# W104C.net
KiCad netlist of a schematic drawn in EAGLE
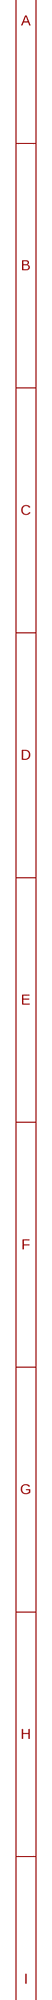
[diagram p0: schematic, sheet 1, part 1 of 2]
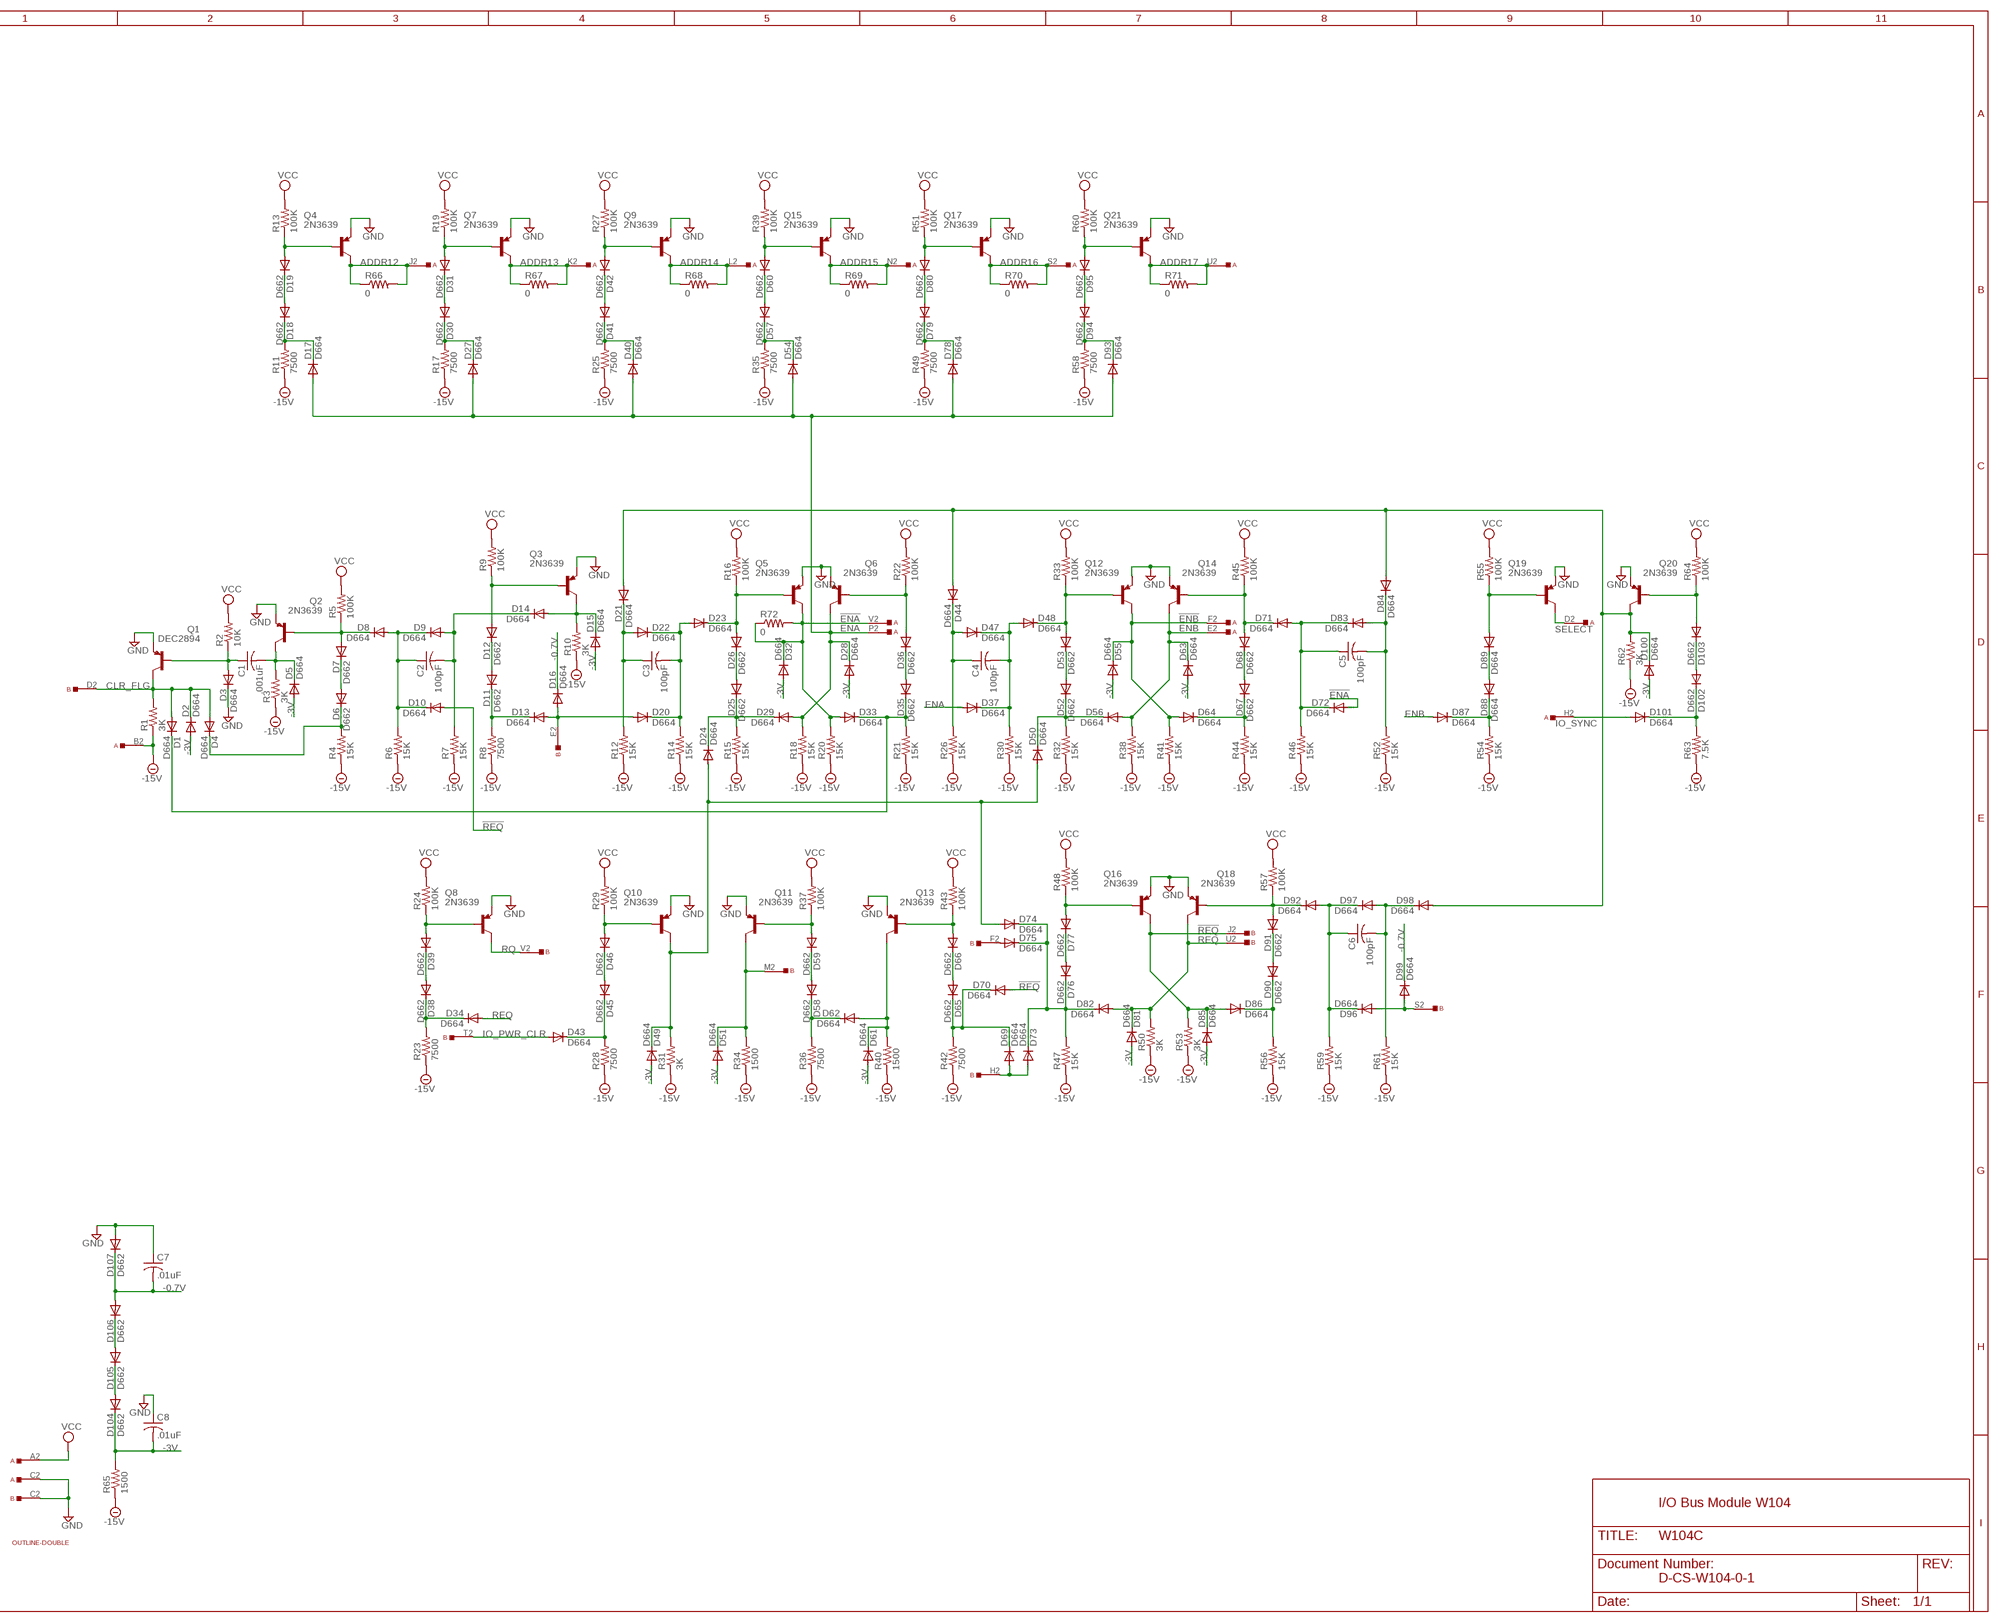
[diagram p1: schematic, sheet 1, part 2 of 2]

(export (version "E")
  (design (tool "Eeschema 10.0.6"))
  (components
    (comp (ref "A")
      (value "SS-TOP")
      (footprint "eagle-import:EDGE-CON1")
      (libsource (lib "eagle-import") (part "SS-TOP"))
    )
    (comp (ref "B")
      (value "SS-TOP")
      (footprint "eagle-import:EDGE-CON1")
      (libsource (lib "eagle-import") (part "SS-TOP"))
    )
    (comp (ref "C1")
      (value ".001uF")
      (footprint "eagle-import:C063-025X075")
      (libsource (lib "eagle-import") (part "C-US"))
    )
    (comp (ref "C2")
      (value "100pF")
      (footprint "eagle-import:C150-054X183")
      (libsource (lib "eagle-import") (part "C-US150-054X183"))
    )
    (comp (ref "C3")
      (value "100pF")
      (footprint "eagle-import:C150-054X183")
      (libsource (lib "eagle-import") (part "C-US150-054X183"))
    )
    (comp (ref "C4")
      (value "100pF")
      (footprint "eagle-import:C150-054X183")
      (libsource (lib "eagle-import") (part "C-US150-054X183"))
    )
    (comp (ref "C5")
      (value "100pF")
      (footprint "eagle-import:C150-054X183")
      (libsource (lib "eagle-import") (part "C-US150-054X183"))
    )
    (comp (ref "C6")
      (value "100pF")
      (footprint "eagle-import:C150-054X183")
      (libsource (lib "eagle-import") (part "C-US150-054X183"))
    )
    (comp (ref "C7")
      (value ".01uF")
      (footprint "eagle-import:C063-025X075")
      (libsource (lib "eagle-import") (part "C-US"))
    )
    (comp (ref "C8")
      (value ".01uF")
      (footprint "eagle-import:C063-025X075")
      (libsource (lib "eagle-import") (part "C-US"))
    )
    (comp (ref "D1")
      (value "D664")
      (footprint "eagle-import:DO35-10")
      (libsource (lib "eagle-import") (part "DIODE-DO35-10"))
    )
    (comp (ref "D2")
      (value "D664")
      (footprint "eagle-import:DO35-10")
      (libsource (lib "eagle-import") (part "DIODE-DO35-10"))
    )
    (comp (ref "D3")
      (value "D664")
      (footprint "eagle-import:DO35-10")
      (libsource (lib "eagle-import") (part "DIODE-DO35-10"))
    )
    (comp (ref "D4")
      (value "D664")
      (footprint "eagle-import:DO35-10")
      (libsource (lib "eagle-import") (part "DIODE-DO35-10"))
    )
    (comp (ref "D5")
      (value "D664")
      (footprint "eagle-import:DO35-10")
      (libsource (lib "eagle-import") (part "DIODE-DO35-10"))
    )
    (comp (ref "D6")
      (value "D662")
      (footprint "eagle-import:DO35-10")
      (libsource (lib "eagle-import") (part "DIODE-DO35-10"))
    )
    (comp (ref "D7")
      (value "D662")
      (footprint "eagle-import:DO35-10")
      (libsource (lib "eagle-import") (part "DIODE-DO35-10"))
    )
    (comp (ref "D8")
      (value "D664")
      (footprint "eagle-import:DO35-10")
      (libsource (lib "eagle-import") (part "DIODE-DO35-10"))
    )
    (comp (ref "D9")
      (value "D664")
      (footprint "eagle-import:DO35-10")
      (libsource (lib "eagle-import") (part "DIODE-DO35-10"))
    )
    (comp (ref "D10")
      (value "D664")
      (footprint "eagle-import:DO35-10")
      (libsource (lib "eagle-import") (part "DIODE-DO35-10"))
    )
    (comp (ref "D11")
      (value "D662")
      (footprint "eagle-import:DO35-10")
      (libsource (lib "eagle-import") (part "DIODE-DO35-10"))
    )
    (comp (ref "D12")
      (value "D662")
      (footprint "eagle-import:DO35-10")
      (libsource (lib "eagle-import") (part "DIODE-DO35-10"))
    )
    (comp (ref "D13")
      (value "D664")
      (footprint "eagle-import:DO35-10")
      (libsource (lib "eagle-import") (part "DIODE-DO35-10"))
    )
    (comp (ref "D14")
      (value "D664")
      (footprint "eagle-import:DO35-10")
      (libsource (lib "eagle-import") (part "DIODE-DO35-10"))
    )
    (comp (ref "D15")
      (value "D664")
      (footprint "eagle-import:DO35-10")
      (libsource (lib "eagle-import") (part "DIODE-DO35-10"))
    )
    (comp (ref "D16")
      (value "D664")
      (footprint "eagle-import:DO35-10")
      (libsource (lib "eagle-import") (part "DIODE-DO35-10"))
    )
    (comp (ref "D17")
      (value "D664")
      (footprint "eagle-import:DO35-10")
      (libsource (lib "eagle-import") (part "DIODE-DO35-10"))
    )
    (comp (ref "D18")
      (value "D662")
      (footprint "eagle-import:DO35-10")
      (libsource (lib "eagle-import") (part "DIODE-DO35-10"))
    )
    (comp (ref "D19")
      (value "D662")
      (footprint "eagle-import:DO35-10")
      (libsource (lib "eagle-import") (part "DIODE-DO35-10"))
    )
    (comp (ref "D20")
      (value "D664")
      (footprint "eagle-import:DO35-10")
      (libsource (lib "eagle-import") (part "DIODE-DO35-10"))
    )
    (comp (ref "D21")
      (value "D664")
      (footprint "eagle-import:DO35-10")
      (libsource (lib "eagle-import") (part "DIODE-DO35-10"))
    )
    (comp (ref "D22")
      (value "D664")
      (footprint "eagle-import:DO35-10")
      (libsource (lib "eagle-import") (part "DIODE-DO35-10"))
    )
    (comp (ref "D23")
      (value "D664")
      (footprint "eagle-import:DO35-10")
      (libsource (lib "eagle-import") (part "DIODE-DO35-10"))
    )
    (comp (ref "D24")
      (value "D664")
      (footprint "eagle-import:DO35-10")
      (libsource (lib "eagle-import") (part "DIODE-DO35-10"))
    )
    (comp (ref "D25")
      (value "D662")
      (footprint "eagle-import:DO35-10")
      (libsource (lib "eagle-import") (part "DIODE-DO35-10"))
    )
    (comp (ref "D26")
      (value "D662")
      (footprint "eagle-import:DO35-10")
      (libsource (lib "eagle-import") (part "DIODE-DO35-10"))
    )
    (comp (ref "D27")
      (value "D664")
      (footprint "eagle-import:DO35-10")
      (libsource (lib "eagle-import") (part "DIODE-DO35-10"))
    )
    (comp (ref "D28")
      (value "D664")
      (footprint "eagle-import:DO35-10")
      (libsource (lib "eagle-import") (part "DIODE-DO35-10"))
    )
    (comp (ref "D29")
      (value "D664")
      (footprint "eagle-import:DO35-10")
      (libsource (lib "eagle-import") (part "DIODE-DO35-10"))
    )
    (comp (ref "D30")
      (value "D662")
      (footprint "eagle-import:DO35-10")
      (libsource (lib "eagle-import") (part "DIODE-DO35-10"))
    )
    (comp (ref "D31")
      (value "D662")
      (footprint "eagle-import:DO35-10")
      (libsource (lib "eagle-import") (part "DIODE-DO35-10"))
    )
    (comp (ref "D32")
      (value "D664")
      (footprint "eagle-import:DO35-10")
      (libsource (lib "eagle-import") (part "DIODE-DO35-10"))
    )
    (comp (ref "D33")
      (value "D664")
      (footprint "eagle-import:DO35-10")
      (libsource (lib "eagle-import") (part "DIODE-DO35-10"))
    )
    (comp (ref "D34")
      (value "D664")
      (footprint "eagle-import:DO35-10")
      (libsource (lib "eagle-import") (part "DIODE-DO35-10"))
    )
    (comp (ref "D35")
      (value "D662")
      (footprint "eagle-import:DO35-10")
      (libsource (lib "eagle-import") (part "DIODE-DO35-10"))
    )
    (comp (ref "D36")
      (value "D662")
      (footprint "eagle-import:DO35-10")
      (libsource (lib "eagle-import") (part "DIODE-DO35-10"))
    )
    (comp (ref "D37")
      (value "D664")
      (footprint "eagle-import:DO35-10")
      (libsource (lib "eagle-import") (part "DIODE-DO35-10"))
    )
    (comp (ref "D38")
      (value "D662")
      (footprint "eagle-import:DO35-10")
      (libsource (lib "eagle-import") (part "DIODE-DO35-10"))
    )
    (comp (ref "D39")
      (value "D662")
      (footprint "eagle-import:DO35-10")
      (libsource (lib "eagle-import") (part "DIODE-DO35-10"))
    )
    (comp (ref "D40")
      (value "D664")
      (footprint "eagle-import:DO35-10")
      (libsource (lib "eagle-import") (part "DIODE-DO35-10"))
    )
    (comp (ref "D41")
      (value "D662")
      (footprint "eagle-import:DO35-10")
      (libsource (lib "eagle-import") (part "DIODE-DO35-10"))
    )
    (comp (ref "D42")
      (value "D662")
      (footprint "eagle-import:DO35-10")
      (libsource (lib "eagle-import") (part "DIODE-DO35-10"))
    )
    (comp (ref "D43")
      (value "D664")
      (footprint "eagle-import:DO35-10")
      (libsource (lib "eagle-import") (part "DIODE-DO35-10"))
    )
    (comp (ref "D44")
      (value "D664")
      (footprint "eagle-import:DO35-10")
      (libsource (lib "eagle-import") (part "DIODE-DO35-10"))
    )
    (comp (ref "D45")
      (value "D662")
      (footprint "eagle-import:DO35-10")
      (libsource (lib "eagle-import") (part "DIODE-DO35-10"))
    )
    (comp (ref "D46")
      (value "D662")
      (footprint "eagle-import:DO35-10")
      (libsource (lib "eagle-import") (part "DIODE-DO35-10"))
    )
    (comp (ref "D47")
      (value "D664")
      (footprint "eagle-import:DO35-10")
      (libsource (lib "eagle-import") (part "DIODE-DO35-10"))
    )
    (comp (ref "D48")
      (value "D664")
      (footprint "eagle-import:DO35-10")
      (libsource (lib "eagle-import") (part "DIODE-DO35-10"))
    )
    (comp (ref "D49")
      (value "D664")
      (footprint "eagle-import:DO35-10")
      (libsource (lib "eagle-import") (part "DIODE-DO35-10"))
    )
    (comp (ref "D50")
      (value "D664")
      (footprint "eagle-import:DO35-10")
      (libsource (lib "eagle-import") (part "DIODE-DO35-10"))
    )
    (comp (ref "D51")
      (value "D664")
      (footprint "eagle-import:DO35-10")
      (libsource (lib "eagle-import") (part "DIODE-DO35-10"))
    )
    (comp (ref "D52")
      (value "D662")
      (footprint "eagle-import:DO35-10")
      (libsource (lib "eagle-import") (part "DIODE-DO35-10"))
    )
    (comp (ref "D53")
      (value "D662")
      (footprint "eagle-import:DO35-10")
      (libsource (lib "eagle-import") (part "DIODE-DO35-10"))
    )
    (comp (ref "D54")
      (value "D664")
      (footprint "eagle-import:DO35-10")
      (libsource (lib "eagle-import") (part "DIODE-DO35-10"))
    )
    (comp (ref "D55")
      (value "D664")
      (footprint "eagle-import:DO35-10")
      (libsource (lib "eagle-import") (part "DIODE-DO35-10"))
    )
    (comp (ref "D56")
      (value "D664")
      (footprint "eagle-import:DO35-10")
      (libsource (lib "eagle-import") (part "DIODE-DO35-10"))
    )
    (comp (ref "D57")
      (value "D662")
      (footprint "eagle-import:DO35-10")
      (libsource (lib "eagle-import") (part "DIODE-DO35-10"))
    )
    (comp (ref "D58")
      (value "D662")
      (footprint "eagle-import:DO35-10")
      (libsource (lib "eagle-import") (part "DIODE-DO35-10"))
    )
    (comp (ref "D59")
      (value "D662")
      (footprint "eagle-import:DO35-10")
      (libsource (lib "eagle-import") (part "DIODE-DO35-10"))
    )
    (comp (ref "D60")
      (value "D662")
      (footprint "eagle-import:DO35-10")
      (libsource (lib "eagle-import") (part "DIODE-DO35-10"))
    )
    (comp (ref "D61")
      (value "D664")
      (footprint "eagle-import:DO35-10")
      (libsource (lib "eagle-import") (part "DIODE-DO35-10"))
    )
    (comp (ref "D62")
      (value "D664")
      (footprint "eagle-import:DO35-10")
      (libsource (lib "eagle-import") (part "DIODE-DO35-10"))
    )
    (comp (ref "D63")
      (value "D664")
      (footprint "eagle-import:DO35-10")
      (libsource (lib "eagle-import") (part "DIODE-DO35-10"))
    )
    (comp (ref "D64")
      (value "D664")
      (footprint "eagle-import:DO35-10")
      (libsource (lib "eagle-import") (part "DIODE-DO35-10"))
    )
    (comp (ref "D65")
      (value "D662")
      (footprint "eagle-import:DO35-10")
      (libsource (lib "eagle-import") (part "DIODE-DO35-10"))
    )
    (comp (ref "D66")
      (value "D662")
      (footprint "eagle-import:DO35-10")
      (libsource (lib "eagle-import") (part "DIODE-DO35-10"))
    )
    (comp (ref "D67")
      (value "D662")
      (footprint "eagle-import:DO35-10")
      (libsource (lib "eagle-import") (part "DIODE-DO35-10"))
    )
    (comp (ref "D68")
      (value "D662")
      (footprint "eagle-import:DO35-10")
      (libsource (lib "eagle-import") (part "DIODE-DO35-10"))
    )
    (comp (ref "D69")
      (value "D664")
      (footprint "eagle-import:DO35-10")
      (libsource (lib "eagle-import") (part "DIODE-DO35-10"))
    )
    (comp (ref "D70")
      (value "D664")
      (footprint "eagle-import:DO35-10")
      (libsource (lib "eagle-import") (part "DIODE-DO35-10"))
    )
    (comp (ref "D71")
      (value "D664")
      (footprint "eagle-import:DO35-10")
      (libsource (lib "eagle-import") (part "DIODE-DO35-10"))
    )
    (comp (ref "D72")
      (value "D664")
      (footprint "eagle-import:DO35-10")
      (libsource (lib "eagle-import") (part "DIODE-DO35-10"))
    )
    (comp (ref "D73")
      (value "D664")
      (footprint "eagle-import:DO35-10")
      (libsource (lib "eagle-import") (part "DIODE-DO35-10"))
    )
    (comp (ref "D74")
      (value "D664")
      (footprint "eagle-import:DO35-10")
      (libsource (lib "eagle-import") (part "DIODE-DO35-10"))
    )
    (comp (ref "D75")
      (value "D664")
      (footprint "eagle-import:DO35-10")
      (libsource (lib "eagle-import") (part "DIODE-DO35-10"))
    )
    (comp (ref "D76")
      (value "D662")
      (footprint "eagle-import:DO35-10")
      (libsource (lib "eagle-import") (part "DIODE-DO35-10"))
    )
    (comp (ref "D77")
      (value "D662")
      (footprint "eagle-import:DO35-10")
      (libsource (lib "eagle-import") (part "DIODE-DO35-10"))
    )
    (comp (ref "D78")
      (value "D664")
      (footprint "eagle-import:DO35-10")
      (libsource (lib "eagle-import") (part "DIODE-DO35-10"))
    )
    (comp (ref "D79")
      (value "D662")
      (footprint "eagle-import:DO35-10")
      (libsource (lib "eagle-import") (part "DIODE-DO35-10"))
    )
    (comp (ref "D80")
      (value "D662")
      (footprint "eagle-import:DO35-10")
      (libsource (lib "eagle-import") (part "DIODE-DO35-10"))
    )
    (comp (ref "D81")
      (value "D664")
      (footprint "eagle-import:DO35-10")
      (libsource (lib "eagle-import") (part "DIODE-DO35-10"))
    )
    (comp (ref "D82")
      (value "D664")
      (footprint "eagle-import:DO35-10")
      (libsource (lib "eagle-import") (part "DIODE-DO35-10"))
    )
    (comp (ref "D83")
      (value "D664")
      (footprint "eagle-import:DO35-10")
      (libsource (lib "eagle-import") (part "DIODE-DO35-10"))
    )
    (comp (ref "D84")
      (value "D664")
      (footprint "eagle-import:DO35-10")
      (libsource (lib "eagle-import") (part "DIODE-DO35-10"))
    )
    (comp (ref "D85")
      (value "D664")
      (footprint "eagle-import:DO35-10")
      (libsource (lib "eagle-import") (part "DIODE-DO35-10"))
    )
    (comp (ref "D86")
      (value "D664")
      (footprint "eagle-import:DO35-10")
      (libsource (lib "eagle-import") (part "DIODE-DO35-10"))
    )
    (comp (ref "D87")
      (value "D664")
      (footprint "eagle-import:DO35-10")
      (libsource (lib "eagle-import") (part "DIODE-DO35-10"))
    )
    (comp (ref "D88")
      (value "D664")
      (footprint "eagle-import:DO35-10")
      (libsource (lib "eagle-import") (part "DIODE-DO35-10"))
    )
    (comp (ref "D89")
      (value "D664")
      (footprint "eagle-import:DO35-10")
      (libsource (lib "eagle-import") (part "DIODE-DO35-10"))
    )
    (comp (ref "D90")
      (value "D662")
      (footprint "eagle-import:DO35-10")
      (libsource (lib "eagle-import") (part "DIODE-DO35-10"))
    )
    (comp (ref "D91")
      (value "D662")
      (footprint "eagle-import:DO35-10")
      (libsource (lib "eagle-import") (part "DIODE-DO35-10"))
    )
    (comp (ref "D92")
      (value "D664")
      (footprint "eagle-import:DO35-10")
      (libsource (lib "eagle-import") (part "DIODE-DO35-10"))
    )
    (comp (ref "D93")
      (value "D664")
      (footprint "eagle-import:DO35-10")
      (libsource (lib "eagle-import") (part "DIODE-DO35-10"))
    )
    (comp (ref "D94")
      (value "D662")
      (footprint "eagle-import:DO35-10")
      (libsource (lib "eagle-import") (part "DIODE-DO35-10"))
    )
    (comp (ref "D95")
      (value "D662")
      (footprint "eagle-import:DO35-10")
      (libsource (lib "eagle-import") (part "DIODE-DO35-10"))
    )
    (comp (ref "D96")
      (value "D664")
      (footprint "eagle-import:DO35-10")
      (libsource (lib "eagle-import") (part "DIODE-DO35-10"))
    )
    (comp (ref "D97")
      (value "D664")
      (footprint "eagle-import:DO35-10")
      (libsource (lib "eagle-import") (part "DIODE-DO35-10"))
    )
    (comp (ref "D98")
      (value "D664")
      (footprint "eagle-import:DO35-10")
      (libsource (lib "eagle-import") (part "DIODE-DO35-10"))
    )
    (comp (ref "D99")
      (value "D664")
      (footprint "eagle-import:DO35-10")
      (libsource (lib "eagle-import") (part "DIODE-DO35-10"))
    )
    (comp (ref "D100")
      (value "D664")
      (footprint "eagle-import:DO35-10")
      (libsource (lib "eagle-import") (part "DIODE-DO35-10"))
    )
    (comp (ref "D101")
      (value "D664")
      (footprint "eagle-import:DO35-10")
      (libsource (lib "eagle-import") (part "DIODE-DO35-10"))
    )
    (comp (ref "D102")
      (value "D662")
      (footprint "eagle-import:DO35-10")
      (libsource (lib "eagle-import") (part "DIODE-DO35-10"))
    )
    (comp (ref "D103")
      (value "D662")
      (footprint "eagle-import:DO35-10")
      (libsource (lib "eagle-import") (part "DIODE-DO35-10"))
    )
    (comp (ref "D104")
      (value "D662")
      (footprint "eagle-import:DO35-10")
      (libsource (lib "eagle-import") (part "DIODE-DO35-10"))
    )
    (comp (ref "D105")
      (value "D662")
      (footprint "eagle-import:DO35-10")
      (libsource (lib "eagle-import") (part "DIODE-DO35-10"))
    )
    (comp (ref "D106")
      (value "D662")
      (footprint "eagle-import:DO35-10")
      (libsource (lib "eagle-import") (part "DIODE-DO35-10"))
    )
    (comp (ref "D107")
      (value "D662")
      (footprint "eagle-import:DO35-10")
      (libsource (lib "eagle-import") (part "DIODE-DO35-10"))
    )
    (comp (ref "Q1")
      (value "DEC2894")
      (footprint "eagle-import:TO5")
      (libsource (lib "eagle-import") (part "-PNP-TO5"))
    )
    (comp (ref "Q2")
      (value "2N3639")
      (footprint "eagle-import:TO5")
      (libsource (lib "eagle-import") (part "-PNP-TO5"))
    )
    (comp (ref "Q3")
      (value "2N3639")
      (footprint "eagle-import:TO5")
      (libsource (lib "eagle-import") (part "-PNP-TO5"))
    )
    (comp (ref "Q4")
      (value "2N3639")
      (footprint "eagle-import:TO5")
      (libsource (lib "eagle-import") (part "-PNP-TO5"))
    )
    (comp (ref "Q5")
      (value "2N3639")
      (footprint "eagle-import:TO5")
      (libsource (lib "eagle-import") (part "-PNP-TO5"))
    )
    (comp (ref "Q6")
      (value "2N3639")
      (footprint "eagle-import:TO5")
      (libsource (lib "eagle-import") (part "-PNP-TO5"))
    )
    (comp (ref "Q7")
      (value "2N3639")
      (footprint "eagle-import:TO5")
      (libsource (lib "eagle-import") (part "-PNP-TO5"))
    )
    (comp (ref "Q8")
      (value "2N3639")
      (footprint "eagle-import:TO5")
      (libsource (lib "eagle-import") (part "-PNP-TO5"))
    )
    (comp (ref "Q9")
      (value "2N3639")
      (footprint "eagle-import:TO5")
      (libsource (lib "eagle-import") (part "-PNP-TO5"))
    )
    (comp (ref "Q10")
      (value "2N3639")
      (footprint "eagle-import:TO5")
      (libsource (lib "eagle-import") (part "-PNP-TO5"))
    )
    (comp (ref "Q11")
      (value "2N3639")
      (footprint "eagle-import:TO5")
      (libsource (lib "eagle-import") (part "-PNP-TO5"))
    )
    (comp (ref "Q12")
      (value "2N3639")
      (footprint "eagle-import:TO5")
      (libsource (lib "eagle-import") (part "-PNP-TO5"))
    )
    (comp (ref "Q13")
      (value "2N3639")
      (footprint "eagle-import:TO5")
      (libsource (lib "eagle-import") (part "-PNP-TO5"))
    )
    (comp (ref "Q14")
      (value "2N3639")
      (footprint "eagle-import:TO5")
      (libsource (lib "eagle-import") (part "-PNP-TO5"))
    )
    (comp (ref "Q15")
      (value "2N3639")
      (footprint "eagle-import:TO5")
      (libsource (lib "eagle-import") (part "-PNP-TO5"))
    )
    (comp (ref "Q16")
      (value "2N3639")
      (footprint "eagle-import:TO5")
      (libsource (lib "eagle-import") (part "-PNP-TO5"))
    )
    (comp (ref "Q17")
      (value "2N3639")
      (footprint "eagle-import:TO5")
      (libsource (lib "eagle-import") (part "-PNP-TO5"))
    )
    (comp (ref "Q18")
      (value "2N3639")
      (footprint "eagle-import:TO5")
      (libsource (lib "eagle-import") (part "-PNP-TO5"))
    )
    (comp (ref "Q19")
      (value "2N3639")
      (footprint "eagle-import:TO5")
      (libsource (lib "eagle-import") (part "-PNP-TO5"))
    )
    (comp (ref "Q20")
      (value "2N3639")
      (footprint "eagle-import:TO5")
      (libsource (lib "eagle-import") (part "-PNP-TO5"))
    )
    (comp (ref "Q21")
      (value "2N3639")
      (footprint "eagle-import:TO5")
      (libsource (lib "eagle-import") (part "-PNP-TO5"))
    )
    (comp (ref "R1")
      (value "3K")
      (footprint "eagle-import:0207_10")
      (libsource (lib "eagle-import") (part "R-US_0207/10"))
    )
    (comp (ref "R2")
      (value "10K")
      (footprint "eagle-import:0207_10")
      (libsource (lib "eagle-import") (part "R-US_0207/10"))
    )
    (comp (ref "R3")
      (value "3K")
      (footprint "eagle-import:0207_10")
      (libsource (lib "eagle-import") (part "R-US_0207/10"))
    )
    (comp (ref "R4")
      (value "15K")
      (footprint "eagle-import:0207_10")
      (libsource (lib "eagle-import") (part "R-US_0207/10"))
    )
    (comp (ref "R5")
      (value "100K")
      (footprint "eagle-import:0207_10")
      (libsource (lib "eagle-import") (part "R-US_0207/10"))
    )
    (comp (ref "R6")
      (value "15K")
      (footprint "eagle-import:0207_10")
      (libsource (lib "eagle-import") (part "R-US_0207/10"))
    )
    (comp (ref "R7")
      (value "15K")
      (footprint "eagle-import:0207_10")
      (libsource (lib "eagle-import") (part "R-US_0207/10"))
    )
    (comp (ref "R8")
      (value "7500")
      (footprint "eagle-import:0207_10")
      (libsource (lib "eagle-import") (part "R-US_0207/10"))
    )
    (comp (ref "R9")
      (value "100K")
      (footprint "eagle-import:0207_10")
      (libsource (lib "eagle-import") (part "R-US_0207/10"))
    )
    (comp (ref "R10")
      (value "3K")
      (footprint "eagle-import:0207_10")
      (libsource (lib "eagle-import") (part "R-US_0207/10"))
    )
    (comp (ref "R11")
      (value "7500")
      (footprint "eagle-import:0207_10")
      (libsource (lib "eagle-import") (part "R-US_0207/10"))
    )
    (comp (ref "R12")
      (value "15K")
      (footprint "eagle-import:0207_10")
      (libsource (lib "eagle-import") (part "R-US_0207/10"))
    )
    (comp (ref "R13")
      (value "100K")
      (footprint "eagle-import:0207_10")
      (libsource (lib "eagle-import") (part "R-US_0207/10"))
    )
    (comp (ref "R14")
      (value "15K")
      (footprint "eagle-import:0207_10")
      (libsource (lib "eagle-import") (part "R-US_0207/10"))
    )
    (comp (ref "R15")
      (value "15K")
      (footprint "eagle-import:0207_10")
      (libsource (lib "eagle-import") (part "R-US_0207/10"))
    )
    (comp (ref "R16")
      (value "100K")
      (footprint "eagle-import:0207_10")
      (libsource (lib "eagle-import") (part "R-US_0207/10"))
    )
    (comp (ref "R17")
      (value "7500")
      (footprint "eagle-import:0207_10")
      (libsource (lib "eagle-import") (part "R-US_0207/10"))
    )
    (comp (ref "R18")
      (value "15K")
      (footprint "eagle-import:0207_10")
      (libsource (lib "eagle-import") (part "R-US_0207/10"))
    )
    (comp (ref "R19")
      (value "100K")
      (footprint "eagle-import:0207_10")
      (libsource (lib "eagle-import") (part "R-US_0207/10"))
    )
    (comp (ref "R20")
      (value "15K")
      (footprint "eagle-import:0207_10")
      (libsource (lib "eagle-import") (part "R-US_0207/10"))
    )
    (comp (ref "R21")
      (value "15K")
      (footprint "eagle-import:0207_10")
      (libsource (lib "eagle-import") (part "R-US_0207/10"))
    )
    (comp (ref "R22")
      (value "100K")
      (footprint "eagle-import:0207_10")
      (libsource (lib "eagle-import") (part "R-US_0207/10"))
    )
    (comp (ref "R23")
      (value "7500")
      (footprint "eagle-import:0207_10")
      (libsource (lib "eagle-import") (part "R-US_0207/10"))
    )
    (comp (ref "R24")
      (value "100K")
      (footprint "eagle-import:0207_10")
      (libsource (lib "eagle-import") (part "R-US_0207/10"))
    )
    (comp (ref "R25")
      (value "7500")
      (footprint "eagle-import:0207_10")
      (libsource (lib "eagle-import") (part "R-US_0207/10"))
    )
    (comp (ref "R26")
      (value "15K")
      (footprint "eagle-import:0207_10")
      (libsource (lib "eagle-import") (part "R-US_0207/10"))
    )
    (comp (ref "R27")
      (value "100K")
      (footprint "eagle-import:0207_10")
      (libsource (lib "eagle-import") (part "R-US_0207/10"))
    )
    (comp (ref "R28")
      (value "7500")
      (footprint "eagle-import:0207_10")
      (libsource (lib "eagle-import") (part "R-US_0207/10"))
    )
    (comp (ref "R29")
      (value "100K")
      (footprint "eagle-import:0207_10")
      (libsource (lib "eagle-import") (part "R-US_0207/10"))
    )
    (comp (ref "R30")
      (value "15K")
      (footprint "eagle-import:0207_10")
      (libsource (lib "eagle-import") (part "R-US_0207/10"))
    )
    (comp (ref "R31")
      (value "3K")
      (footprint "eagle-import:0207_10")
      (libsource (lib "eagle-import") (part "R-US_0207/10"))
    )
    (comp (ref "R32")
      (value "15K")
      (footprint "eagle-import:0207_10")
      (libsource (lib "eagle-import") (part "R-US_0207/10"))
    )
    (comp (ref "R33")
      (value "100K")
      (footprint "eagle-import:0207_10")
      (libsource (lib "eagle-import") (part "R-US_0207/10"))
    )
    (comp (ref "R34")
      (value "1500")
      (footprint "eagle-import:0207_10")
      (libsource (lib "eagle-import") (part "R-US_0207/10"))
    )
    (comp (ref "R35")
      (value "7500")
      (footprint "eagle-import:0207_10")
      (libsource (lib "eagle-import") (part "R-US_0207/10"))
    )
    (comp (ref "R36")
      (value "7500")
      (footprint "eagle-import:0207_10")
      (libsource (lib "eagle-import") (part "R-US_0207/10"))
    )
    (comp (ref "R37")
      (value "100K")
      (footprint "eagle-import:0207_10")
      (libsource (lib "eagle-import") (part "R-US_0207/10"))
    )
    (comp (ref "R38")
      (value "15K")
      (footprint "eagle-import:0207_10")
      (libsource (lib "eagle-import") (part "R-US_0207/10"))
    )
    (comp (ref "R39")
      (value "100K")
      (footprint "eagle-import:0207_10")
      (libsource (lib "eagle-import") (part "R-US_0207/10"))
    )
    (comp (ref "R40")
      (value "1500")
      (footprint "eagle-import:0207_10")
      (libsource (lib "eagle-import") (part "R-US_0207/10"))
    )
    (comp (ref "R41")
      (value "15K")
      (footprint "eagle-import:0207_10")
      (libsource (lib "eagle-import") (part "R-US_0207/10"))
    )
    (comp (ref "R42")
      (value "7500")
      (footprint "eagle-import:0207_10")
      (libsource (lib "eagle-import") (part "R-US_0207/10"))
    )
    (comp (ref "R43")
      (value "100K")
      (footprint "eagle-import:0207_10")
      (libsource (lib "eagle-import") (part "R-US_0207/10"))
    )
    (comp (ref "R44")
      (value "15K")
      (footprint "eagle-import:0207_10")
      (libsource (lib "eagle-import") (part "R-US_0207/10"))
    )
    (comp (ref "R45")
      (value "100K")
      (footprint "eagle-import:0207_10")
      (libsource (lib "eagle-import") (part "R-US_0207/10"))
    )
    (comp (ref "R46")
      (value "15K")
      (footprint "eagle-import:0207_10")
      (libsource (lib "eagle-import") (part "R-US_0207/10"))
    )
    (comp (ref "R47")
      (value "15K")
      (footprint "eagle-import:0207_10")
      (libsource (lib "eagle-import") (part "R-US_0207/10"))
    )
    (comp (ref "R48")
      (value "100K")
      (footprint "eagle-import:0207_10")
      (libsource (lib "eagle-import") (part "R-US_0207/10"))
    )
    (comp (ref "R49")
      (value "7500")
      (footprint "eagle-import:0207_10")
      (libsource (lib "eagle-import") (part "R-US_0207/10"))
    )
    (comp (ref "R50")
      (value "3K")
      (footprint "eagle-import:0207_10")
      (libsource (lib "eagle-import") (part "R-US_0207/10"))
    )
    (comp (ref "R51")
      (value "100K")
      (footprint "eagle-import:0207_10")
      (libsource (lib "eagle-import") (part "R-US_0207/10"))
    )
    (comp (ref "R52")
      (value "15K")
      (footprint "eagle-import:0207_10")
      (libsource (lib "eagle-import") (part "R-US_0207/10"))
    )
    (comp (ref "R53")
      (value "3K")
      (footprint "eagle-import:0207_10")
      (libsource (lib "eagle-import") (part "R-US_0207/10"))
    )
    (comp (ref "R54")
      (value "15K")
      (footprint "eagle-import:0207_10")
      (libsource (lib "eagle-import") (part "R-US_0207/10"))
    )
    (comp (ref "R55")
      (value "100K")
      (footprint "eagle-import:0207_10")
      (libsource (lib "eagle-import") (part "R-US_0207/10"))
    )
    (comp (ref "R56")
      (value "15K")
      (footprint "eagle-import:0207_10")
      (libsource (lib "eagle-import") (part "R-US_0207/10"))
    )
    (comp (ref "R57")
      (value "100K")
      (footprint "eagle-import:0207_10")
      (libsource (lib "eagle-import") (part "R-US_0207/10"))
    )
    (comp (ref "R58")
      (value "7500")
      (footprint "eagle-import:0207_10")
      (libsource (lib "eagle-import") (part "R-US_0207/10"))
    )
    (comp (ref "R59")
      (value "15K")
      (footprint "eagle-import:0207_10")
      (libsource (lib "eagle-import") (part "R-US_0207/10"))
    )
    (comp (ref "R60")
      (value "100K")
      (footprint "eagle-import:0207_10")
      (libsource (lib "eagle-import") (part "R-US_0207/10"))
    )
    (comp (ref "R61")
      (value "15K")
      (footprint "eagle-import:0207_10")
      (libsource (lib "eagle-import") (part "R-US_0207/10"))
    )
    (comp (ref "R62")
      (value "3K")
      (footprint "eagle-import:0207_10")
      (libsource (lib "eagle-import") (part "R-US_0207/10"))
    )
    (comp (ref "R63")
      (value "7.5K")
      (footprint "eagle-import:0207_10")
      (libsource (lib "eagle-import") (part "R-US_0207/10"))
    )
    (comp (ref "R64")
      (value "100K")
      (footprint "eagle-import:0207_10")
      (libsource (lib "eagle-import") (part "R-US_0207/10"))
    )
    (comp (ref "R65")
      (value "1500")
      (footprint "eagle-import:0207_10")
      (libsource (lib "eagle-import") (part "R-US_0207/10"))
    )
    (comp (ref "R66")
      (value "0")
      (footprint "eagle-import:0207_10")
      (libsource (lib "eagle-import") (part "R-US_0207/10"))
    )
    (comp (ref "R67")
      (value "0")
      (footprint "eagle-import:0207_10")
      (libsource (lib "eagle-import") (part "R-US_0207/10"))
    )
    (comp (ref "R68")
      (value "0")
      (footprint "eagle-import:0207_10")
      (libsource (lib "eagle-import") (part "R-US_0207/10"))
    )
    (comp (ref "R69")
      (value "0")
      (footprint "eagle-import:0207_10")
      (libsource (lib "eagle-import") (part "R-US_0207/10"))
    )
    (comp (ref "R70")
      (value "0")
      (footprint "eagle-import:0207_10")
      (libsource (lib "eagle-import") (part "R-US_0207/10"))
    )
    (comp (ref "R71")
      (value "0")
      (footprint "eagle-import:0207_10")
      (libsource (lib "eagle-import") (part "R-US_0207/10"))
    )
    (comp (ref "R72")
      (value "0")
      (footprint "eagle-import:0207_10")
      (libsource (lib "eagle-import") (part "R-US_0207/10"))
    )
    (comp (ref "U$1")
      (value "OUTLINE-DOUBLE")
      (footprint "eagle-import:DOUBLE")
      (libsource (lib "eagle-import") (part "OUTLINE-DOUBLE"))
    )
  )
  (nets
    (net (code "1") (name "-15V") (class "Default")
      (node (ref "A") (pin "B2") (pinfunction "P_B2") (pintype "passive"))
      (node (ref "R1") (pin "1") (pinfunction "1_1") (pintype "passive"))
      (node (ref "R10") (pin "1") (pinfunction "1_1") (pintype "passive"))
      (node (ref "R11") (pin "1") (pinfunction "1_1") (pintype "passive"))
      (node (ref "R12") (pin "1") (pinfunction "1_1") (pintype "passive"))
      (node (ref "R14") (pin "1") (pinfunction "1_1") (pintype "passive"))
      (node (ref "R15") (pin "1") (pinfunction "1_1") (pintype "passive"))
      (node (ref "R17") (pin "1") (pinfunction "1_1") (pintype "passive"))
      (node (ref "R18") (pin "1") (pinfunction "1_1") (pintype "passive"))
      (node (ref "R20") (pin "1") (pinfunction "1_1") (pintype "passive"))
      (node (ref "R21") (pin "1") (pinfunction "1_1") (pintype "passive"))
      (node (ref "R23") (pin "1") (pinfunction "1_1") (pintype "passive"))
      (node (ref "R25") (pin "1") (pinfunction "1_1") (pintype "passive"))
      (node (ref "R26") (pin "1") (pinfunction "1_1") (pintype "passive"))
      (node (ref "R28") (pin "1") (pinfunction "1_1") (pintype "passive"))
      (node (ref "R3") (pin "1") (pinfunction "1_1") (pintype "passive"))
      (node (ref "R30") (pin "1") (pinfunction "1_1") (pintype "passive"))
      (node (ref "R31") (pin "1") (pinfunction "1_1") (pintype "passive"))
      (node (ref "R32") (pin "1") (pinfunction "1_1") (pintype "passive"))
      (node (ref "R34") (pin "1") (pinfunction "1_1") (pintype "passive"))
      (node (ref "R35") (pin "1") (pinfunction "1_1") (pintype "passive"))
      (node (ref "R36") (pin "1") (pinfunction "1_1") (pintype "passive"))
      (node (ref "R38") (pin "1") (pinfunction "1_1") (pintype "passive"))
      (node (ref "R4") (pin "1") (pinfunction "1_1") (pintype "passive"))
      (node (ref "R40") (pin "1") (pinfunction "1_1") (pintype "passive"))
      (node (ref "R41") (pin "1") (pinfunction "1_1") (pintype "passive"))
      (node (ref "R42") (pin "1") (pinfunction "1_1") (pintype "passive"))
      (node (ref "R44") (pin "1") (pinfunction "1_1") (pintype "passive"))
      (node (ref "R46") (pin "1") (pinfunction "1_1") (pintype "passive"))
      (node (ref "R47") (pin "1") (pinfunction "1_1") (pintype "passive"))
      (node (ref "R49") (pin "1") (pinfunction "1_1") (pintype "passive"))
      (node (ref "R50") (pin "1") (pinfunction "1_1") (pintype "passive"))
      (node (ref "R52") (pin "1") (pinfunction "1_1") (pintype "passive"))
      (node (ref "R53") (pin "1") (pinfunction "1_1") (pintype "passive"))
      (node (ref "R54") (pin "1") (pinfunction "1_1") (pintype "passive"))
      (node (ref "R56") (pin "1") (pinfunction "1_1") (pintype "passive"))
      (node (ref "R58") (pin "1") (pinfunction "1_1") (pintype "passive"))
      (node (ref "R59") (pin "1") (pinfunction "1_1") (pintype "passive"))
      (node (ref "R6") (pin "1") (pinfunction "1_1") (pintype "passive"))
      (node (ref "R61") (pin "1") (pinfunction "1_1") (pintype "passive"))
      (node (ref "R62") (pin "1") (pinfunction "1_1") (pintype "passive"))
      (node (ref "R63") (pin "1") (pinfunction "1_1") (pintype "passive"))
      (node (ref "R65") (pin "1") (pinfunction "1_1") (pintype "passive"))
      (node (ref "R7") (pin "1") (pinfunction "1_1") (pintype "passive"))
      (node (ref "R8") (pin "1") (pinfunction "1_1") (pintype "passive"))
    )
    (net (code "2") (name "/-0.7V") (class "Default")
      (node (ref "C7") (pin "2") (pinfunction "2_2") (pintype "passive"))
      (node (ref "D106") (pin "A") (pinfunction "A_A") (pintype "passive"))
      (node (ref "D107") (pin "C") (pinfunction "C_C") (pintype "passive"))
      (node (ref "D16") (pin "C") (pinfunction "C_C") (pintype "passive"))
      (node (ref "D99") (pin "C") (pinfunction "C_C") (pintype "passive"))
    )
    (net (code "3") (name "/-3V") (class "Default")
      (node (ref "C8") (pin "2") (pinfunction "2_2") (pintype "passive"))
      (node (ref "D100") (pin "A") (pinfunction "A_A") (pintype "passive"))
      (node (ref "D104") (pin "C") (pinfunction "C_C") (pintype "passive"))
      (node (ref "D15") (pin "A") (pinfunction "A_A") (pintype "passive"))
      (node (ref "D2") (pin "A") (pinfunction "A_A") (pintype "passive"))
      (node (ref "D28") (pin "A") (pinfunction "A_A") (pintype "passive"))
      (node (ref "D32") (pin "A") (pinfunction "A_A") (pintype "passive"))
      (node (ref "D49") (pin "A") (pinfunction "A_A") (pintype "passive"))
      (node (ref "D5") (pin "A") (pinfunction "A_A") (pintype "passive"))
      (node (ref "D51") (pin "A") (pinfunction "A_A") (pintype "passive"))
      (node (ref "D55") (pin "A") (pinfunction "A_A") (pintype "passive"))
      (node (ref "D61") (pin "A") (pinfunction "A_A") (pintype "passive"))
      (node (ref "D63") (pin "A") (pinfunction "A_A") (pintype "passive"))
      (node (ref "D81") (pin "A") (pinfunction "A_A") (pintype "passive"))
      (node (ref "D85") (pin "A") (pinfunction "A_A") (pintype "passive"))
      (node (ref "R65") (pin "2") (pinfunction "2_2") (pintype "passive"))
    )
    (net (code "4") (name "/ADDR12") (class "Default")
      (node (ref "A") (pin "J2") (pinfunction "P_J2") (pintype "passive"))
      (node (ref "Q4") (pin "3") (pinfunction "C_3") (pintype "passive"))
      (node (ref "R66") (pin "1") (pinfunction "1_1") (pintype "passive"))
      (node (ref "R66") (pin "2") (pinfunction "2_2") (pintype "passive"))
    )
    (net (code "5") (name "/ADDR13") (class "Default")
      (node (ref "A") (pin "K2") (pinfunction "P_K2") (pintype "passive"))
      (node (ref "Q7") (pin "3") (pinfunction "C_3") (pintype "passive"))
      (node (ref "R67") (pin "1") (pinfunction "1_1") (pintype "passive"))
      (node (ref "R67") (pin "2") (pinfunction "2_2") (pintype "passive"))
    )
    (net (code "6") (name "/ADDR14") (class "Default")
      (node (ref "A") (pin "L2") (pinfunction "P_L2") (pintype "passive"))
      (node (ref "Q9") (pin "3") (pinfunction "C_3") (pintype "passive"))
      (node (ref "R68") (pin "1") (pinfunction "1_1") (pintype "passive"))
      (node (ref "R68") (pin "2") (pinfunction "2_2") (pintype "passive"))
    )
    (net (code "7") (name "/ADDR15") (class "Default")
      (node (ref "A") (pin "N2") (pinfunction "P_N2") (pintype "passive"))
      (node (ref "Q15") (pin "3") (pinfunction "C_3") (pintype "passive"))
      (node (ref "R69") (pin "1") (pinfunction "1_1") (pintype "passive"))
      (node (ref "R69") (pin "2") (pinfunction "2_2") (pintype "passive"))
    )
    (net (code "8") (name "/ADDR16") (class "Default")
      (node (ref "A") (pin "S2") (pinfunction "P_S2") (pintype "passive"))
      (node (ref "Q17") (pin "3") (pinfunction "C_3") (pintype "passive"))
      (node (ref "R70") (pin "1") (pinfunction "1_1") (pintype "passive"))
      (node (ref "R70") (pin "2") (pinfunction "2_2") (pintype "passive"))
    )
    (net (code "9") (name "/ADDR17") (class "Default")
      (node (ref "A") (pin "U2") (pinfunction "P_U2") (pintype "passive"))
      (node (ref "Q21") (pin "3") (pinfunction "C_3") (pintype "passive"))
      (node (ref "R71") (pin "1") (pinfunction "1_1") (pintype "passive"))
      (node (ref "R71") (pin "2") (pinfunction "2_2") (pintype "passive"))
    )
    (net (code "10") (name "/CLR_FLG") (class "Default")
      (node (ref "B") (pin "D2") (pinfunction "P_D2") (pintype "passive"))
      (node (ref "D1") (pin "A") (pinfunction "A_A") (pintype "passive"))
      (node (ref "D2") (pin "C") (pinfunction "C_C") (pintype "passive"))
      (node (ref "D4") (pin "A") (pinfunction "A_A") (pintype "passive"))
      (node (ref "Q1") (pin "3") (pinfunction "C_3") (pintype "passive"))
      (node (ref "R1") (pin "2") (pinfunction "2_2") (pintype "passive"))
    )
    (net (code "11") (name "/ENA") (class "Default")
      (node (ref "A") (pin "P2") (pinfunction "P_P2") (pintype "passive"))
      (node (ref "D17") (pin "A") (pinfunction "A_A") (pintype "passive"))
      (node (ref "D27") (pin "A") (pinfunction "A_A") (pintype "passive"))
      (node (ref "D28") (pin "C") (pinfunction "C_C") (pintype "passive"))
      (node (ref "D29") (pin "A") (pinfunction "A_A") (pintype "passive"))
      (node (ref "D37") (pin "A") (pinfunction "A_A") (pintype "passive"))
      (node (ref "D40") (pin "A") (pinfunction "A_A") (pintype "passive"))
      (node (ref "D54") (pin "A") (pinfunction "A_A") (pintype "passive"))
      (node (ref "D78") (pin "A") (pinfunction "A_A") (pintype "passive"))
      (node (ref "D93") (pin "A") (pinfunction "A_A") (pintype "passive"))
      (node (ref "Q6") (pin "3") (pinfunction "C_3") (pintype "passive"))
      (node (ref "R18") (pin "2") (pinfunction "2_2") (pintype "passive"))
    )
    (net (code "12") (name "/ENB") (class "Default")
      (node (ref "A") (pin "E2") (pinfunction "P_E2") (pintype "passive"))
      (node (ref "D56") (pin "A") (pinfunction "A_A") (pintype "passive"))
      (node (ref "D63") (pin "C") (pinfunction "C_C") (pintype "passive"))
      (node (ref "D87") (pin "A") (pinfunction "A_A") (pintype "passive"))
      (node (ref "Q14") (pin "3") (pinfunction "C_3") (pintype "passive"))
      (node (ref "R38") (pin "2") (pinfunction "2_2") (pintype "passive"))
    )
    (net (code "13") (name "/IO_PWR_CLR") (class "Default")
      (node (ref "B") (pin "T2") (pinfunction "P_T2") (pintype "passive"))
      (node (ref "D43") (pin "A") (pinfunction "A_A") (pintype "passive"))
    )
    (net (code "14") (name "/IO_SYNC") (class "Default")
      (node (ref "A") (pin "H2") (pinfunction "P_H2") (pintype "passive"))
      (node (ref "D101") (pin "A") (pinfunction "A_A") (pintype "passive"))
    )
    (net (code "15") (name "/REQ") (class "Default")
      (node (ref "B") (pin "U2") (pinfunction "P_U2") (pintype "passive"))
      (node (ref "D34") (pin "A") (pinfunction "A_A") (pintype "passive"))
      (node (ref "D81") (pin "C") (pinfunction "C_C") (pintype "passive"))
      (node (ref "D82") (pin "A") (pinfunction "A_A") (pintype "passive"))
      (node (ref "Q18") (pin "3") (pinfunction "C_3") (pintype "passive"))
      (node (ref "R50") (pin "2") (pinfunction "2_2") (pintype "passive"))
    )
    (net (code "16") (name "/RQ") (class "Default")
      (node (ref "B") (pin "V2") (pinfunction "P_V2") (pintype "passive"))
      (node (ref "Q8") (pin "3") (pinfunction "C_3") (pintype "passive"))
    )
    (net (code "17") (name "/SELECT") (class "Default")
      (node (ref "A") (pin "D2") (pinfunction "P_D2") (pintype "passive"))
      (node (ref "Q19") (pin "3") (pinfunction "C_3") (pintype "passive"))
    )
    (net (code "18") (name "/~{ENA}") (class "Default")
      (node (ref "A") (pin "V2") (pinfunction "P_V2") (pintype "passive"))
      (node (ref "D32") (pin "C") (pinfunction "C_C") (pintype "passive"))
      (node (ref "D33") (pin "A") (pinfunction "A_A") (pintype "passive"))
      (node (ref "D72") (pin "A") (pinfunction "A_A") (pintype "passive"))
      (node (ref "Q5") (pin "3") (pinfunction "C_3") (pintype "passive"))
      (node (ref "R20") (pin "2") (pinfunction "2_2") (pintype "passive"))
      (node (ref "R72") (pin "1") (pinfunction "1_1") (pintype "passive"))
      (node (ref "R72") (pin "2") (pinfunction "2_2") (pintype "passive"))
    )
    (net (code "19") (name "/~{ENB}") (class "Default")
      (node (ref "A") (pin "F2") (pinfunction "P_F2") (pintype "passive"))
      (node (ref "D55") (pin "C") (pinfunction "C_C") (pintype "passive"))
      (node (ref "D64") (pin "A") (pinfunction "A_A") (pintype "passive"))
      (node (ref "Q12") (pin "3") (pinfunction "C_3") (pintype "passive"))
      (node (ref "R41") (pin "2") (pinfunction "2_2") (pintype "passive"))
    )
    (net (code "20") (name "/~{REQ}") (class "Default")
      (node (ref "B") (pin "J2") (pinfunction "P_J2") (pintype "passive"))
      (node (ref "D10") (pin "A") (pinfunction "A_A") (pintype "passive"))
      (node (ref "D70") (pin "A") (pinfunction "A_A") (pintype "passive"))
      (node (ref "D85") (pin "C") (pinfunction "C_C") (pintype "passive"))
      (node (ref "D86") (pin "A") (pinfunction "A_A") (pintype "passive"))
      (node (ref "Q16") (pin "3") (pinfunction "C_3") (pintype "passive"))
      (node (ref "R53") (pin "2") (pinfunction "2_2") (pintype "passive"))
    )
    (net (code "21") (name "GND") (class "Default")
      (node (ref "A") (pin "C2") (pinfunction "P_C2") (pintype "passive"))
      (node (ref "B") (pin "C2") (pinfunction "P_C2") (pintype "passive"))
      (node (ref "C7") (pin "1") (pinfunction "1_1") (pintype "passive"))
      (node (ref "C8") (pin "1") (pinfunction "1_1") (pintype "passive"))
      (node (ref "D107") (pin "A") (pinfunction "A_A") (pintype "passive"))
      (node (ref "D3") (pin "C") (pinfunction "C_C") (pintype "passive"))
      (node (ref "Q1") (pin "1") (pinfunction "E_1") (pintype "passive"))
      (node (ref "Q10") (pin "1") (pinfunction "E_1") (pintype "passive"))
      (node (ref "Q11") (pin "1") (pinfunction "E_1") (pintype "passive"))
      (node (ref "Q12") (pin "1") (pinfunction "E_1") (pintype "passive"))
      (node (ref "Q13") (pin "1") (pinfunction "E_1") (pintype "passive"))
      (node (ref "Q14") (pin "1") (pinfunction "E_1") (pintype "passive"))
      (node (ref "Q15") (pin "1") (pinfunction "E_1") (pintype "passive"))
      (node (ref "Q16") (pin "1") (pinfunction "E_1") (pintype "passive"))
      (node (ref "Q17") (pin "1") (pinfunction "E_1") (pintype "passive"))
      (node (ref "Q18") (pin "1") (pinfunction "E_1") (pintype "passive"))
      (node (ref "Q19") (pin "1") (pinfunction "E_1") (pintype "passive"))
      (node (ref "Q2") (pin "1") (pinfunction "E_1") (pintype "passive"))
      (node (ref "Q20") (pin "1") (pinfunction "E_1") (pintype "passive"))
      (node (ref "Q21") (pin "1") (pinfunction "E_1") (pintype "passive"))
      (node (ref "Q3") (pin "1") (pinfunction "E_1") (pintype "passive"))
      (node (ref "Q4") (pin "1") (pinfunction "E_1") (pintype "passive"))
      (node (ref "Q5") (pin "1") (pinfunction "E_1") (pintype "passive"))
      (node (ref "Q6") (pin "1") (pinfunction "E_1") (pintype "passive"))
      (node (ref "Q7") (pin "1") (pinfunction "E_1") (pintype "passive"))
      (node (ref "Q8") (pin "1") (pinfunction "E_1") (pintype "passive"))
      (node (ref "Q9") (pin "1") (pinfunction "E_1") (pintype "passive"))
    )
    (net (code "22") (name "Net-(BE-P)") (class "Default")
      (node (ref "B") (pin "E2") (pinfunction "P_E2") (pintype "passive"))
      (node (ref "D13") (pin "A") (pinfunction "A_A") (pintype "passive"))
      (node (ref "D16") (pin "A") (pinfunction "A_A") (pintype "passive"))
      (node (ref "D20") (pin "A") (pinfunction "A_A") (pintype "passive"))
    )
    (net (code "23") (name "Net-(BF-P)") (class "Default")
      (node (ref "B") (pin "F2") (pinfunction "P_F2") (pintype "passive"))
      (node (ref "D75") (pin "A") (pinfunction "A_A") (pintype "passive"))
    )
    (net (code "24") (name "Net-(BG-P)") (class "Default")
      (node (ref "B") (pin "H2") (pinfunction "P_H2") (pintype "passive"))
      (node (ref "D69") (pin "A") (pinfunction "A_A") (pintype "passive"))
      (node (ref "D73") (pin "A") (pinfunction "A_A") (pintype "passive"))
    )
    (net (code "25") (name "Net-(BK-P)") (class "Default")
      (node (ref "B") (pin "M2") (pinfunction "P_M2") (pintype "passive"))
      (node (ref "D51") (pin "C") (pinfunction "C_C") (pintype "passive"))
      (node (ref "Q11") (pin "3") (pinfunction "C_3") (pintype "passive"))
      (node (ref "R34") (pin "2") (pinfunction "2_2") (pintype "passive"))
    )
    (net (code "26") (name "Net-(BO-P)") (class "Default")
      (node (ref "B") (pin "S2") (pinfunction "P_S2") (pintype "passive"))
      (node (ref "D96") (pin "A") (pinfunction "A_A") (pintype "passive"))
      (node (ref "D99") (pin "A") (pinfunction "A_A") (pintype "passive"))
    )
    (net (code "27") (name "Net-(C2-Pad1)") (class "Default")
      (node (ref "C2") (pin "1") (pinfunction "1_1") (pintype "passive"))
      (node (ref "D10") (pin "C") (pinfunction "C_C") (pintype "passive"))
      (node (ref "D8") (pin "A") (pinfunction "A_A") (pintype "passive"))
      (node (ref "D9") (pin "C") (pinfunction "C_C") (pintype "passive"))
      (node (ref "R6") (pin "2") (pinfunction "2_2") (pintype "passive"))
    )
    (net (code "28") (name "Net-(C2-Pad2)") (class "Default")
      (node (ref "C2") (pin "2") (pinfunction "2_2") (pintype "passive"))
      (node (ref "D14") (pin "C") (pinfunction "C_C") (pintype "passive"))
      (node (ref "D9") (pin "A") (pinfunction "A_A") (pintype "passive"))
      (node (ref "R7") (pin "2") (pinfunction "2_2") (pintype "passive"))
    )
    (net (code "29") (name "Net-(C3-Pad1)") (class "Default")
      (node (ref "C3") (pin "1") (pinfunction "1_1") (pintype "passive"))
      (node (ref "D21") (pin "C") (pinfunction "C_C") (pintype "passive"))
      (node (ref "D22") (pin "A") (pinfunction "A_A") (pintype "passive"))
      (node (ref "R12") (pin "2") (pinfunction "2_2") (pintype "passive"))
    )
    (net (code "30") (name "Net-(C3-Pad2)") (class "Default")
      (node (ref "C3") (pin "2") (pinfunction "2_2") (pintype "passive"))
      (node (ref "D20") (pin "C") (pinfunction "C_C") (pintype "passive"))
      (node (ref "D22") (pin "C") (pinfunction "C_C") (pintype "passive"))
      (node (ref "D23") (pin "A") (pinfunction "A_A") (pintype "passive"))
      (node (ref "R14") (pin "2") (pinfunction "2_2") (pintype "passive"))
    )
    (net (code "31") (name "Net-(C4-Pad1)") (class "Default")
      (node (ref "C4") (pin "1") (pinfunction "1_1") (pintype "passive"))
      (node (ref "D44") (pin "C") (pinfunction "C_C") (pintype "passive"))
      (node (ref "D47") (pin "A") (pinfunction "A_A") (pintype "passive"))
      (node (ref "R26") (pin "2") (pinfunction "2_2") (pintype "passive"))
    )
    (net (code "32") (name "Net-(C4-Pad2)") (class "Default")
      (node (ref "C4") (pin "2") (pinfunction "2_2") (pintype "passive"))
      (node (ref "D37") (pin "C") (pinfunction "C_C") (pintype "passive"))
      (node (ref "D47") (pin "C") (pinfunction "C_C") (pintype "passive"))
      (node (ref "D48") (pin "A") (pinfunction "A_A") (pintype "passive"))
      (node (ref "R30") (pin "2") (pinfunction "2_2") (pintype "passive"))
    )
    (net (code "33") (name "Net-(C5-Pad1)") (class "Default")
      (node (ref "C5") (pin "1") (pinfunction "1_1") (pintype "passive"))
      (node (ref "D71") (pin "A") (pinfunction "A_A") (pintype "passive"))
      (node (ref "D72") (pin "C") (pinfunction "C_C") (pintype "passive"))
      (node (ref "D83") (pin "C") (pinfunction "C_C") (pintype "passive"))
      (node (ref "R46") (pin "2") (pinfunction "2_2") (pintype "passive"))
    )
    (net (code "34") (name "Net-(C5-Pad2)") (class "Default")
      (node (ref "C5") (pin "2") (pinfunction "2_2") (pintype "passive"))
      (node (ref "D83") (pin "A") (pinfunction "A_A") (pintype "passive"))
      (node (ref "D84") (pin "C") (pinfunction "C_C") (pintype "passive"))
      (node (ref "R52") (pin "2") (pinfunction "2_2") (pintype "passive"))
    )
    (net (code "35") (name "Net-(C6-Pad1)") (class "Default")
      (node (ref "C6") (pin "1") (pinfunction "1_1") (pintype "passive"))
      (node (ref "D92") (pin "A") (pinfunction "A_A") (pintype "passive"))
      (node (ref "D96") (pin "C") (pinfunction "C_C") (pintype "passive"))
      (node (ref "D97") (pin "C") (pinfunction "C_C") (pintype "passive"))
      (node (ref "R59") (pin "2") (pinfunction "2_2") (pintype "passive"))
    )
    (net (code "36") (name "Net-(C6-Pad2)") (class "Default")
      (node (ref "C6") (pin "2") (pinfunction "2_2") (pintype "passive"))
      (node (ref "D97") (pin "A") (pinfunction "A_A") (pintype "passive"))
      (node (ref "D98") (pin "C") (pinfunction "C_C") (pintype "passive"))
      (node (ref "R61") (pin "2") (pinfunction "2_2") (pintype "passive"))
    )
    (net (code "37") (name "Net-(D1-PadC)") (class "Default")
      (node (ref "D1") (pin "C") (pinfunction "C_C") (pintype "passive"))
      (node (ref "D33") (pin "C") (pinfunction "C_C") (pintype "passive"))
      (node (ref "D35") (pin "C") (pinfunction "C_C") (pintype "passive"))
      (node (ref "R21") (pin "2") (pinfunction "2_2") (pintype "passive"))
    )
    (net (code "38") (name "Net-(D4-PadC)") (class "Default")
      (node (ref "D4") (pin "C") (pinfunction "C_C") (pintype "passive"))
      (node (ref "D6") (pin "C") (pinfunction "C_C") (pintype "passive"))
      (node (ref "R4") (pin "2") (pinfunction "2_2") (pintype "passive"))
    )
    (net (code "39") (name "Net-(D6-PadA)") (class "Default")
      (node (ref "D6") (pin "A") (pinfunction "A_A") (pintype "passive"))
      (node (ref "D7") (pin "C") (pinfunction "C_C") (pintype "passive"))
    )
    (net (code "40") (name "Net-(D11-PadA)") (class "Default")
      (node (ref "D11") (pin "A") (pinfunction "A_A") (pintype "passive"))
      (node (ref "D12") (pin "C") (pinfunction "C_C") (pintype "passive"))
    )
    (net (code "41") (name "Net-(D11-PadC)") (class "Default")
      (node (ref "D11") (pin "C") (pinfunction "C_C") (pintype "passive"))
      (node (ref "D13") (pin "C") (pinfunction "C_C") (pintype "passive"))
      (node (ref "R8") (pin "2") (pinfunction "2_2") (pintype "passive"))
    )
    (net (code "42") (name "Net-(D17-PadC)") (class "Default")
      (node (ref "D17") (pin "C") (pinfunction "C_C") (pintype "passive"))
      (node (ref "D18") (pin "C") (pinfunction "C_C") (pintype "passive"))
      (node (ref "R11") (pin "2") (pinfunction "2_2") (pintype "passive"))
    )
    (net (code "43") (name "Net-(D18-PadA)") (class "Default")
      (node (ref "D18") (pin "A") (pinfunction "A_A") (pintype "passive"))
      (node (ref "D19") (pin "C") (pinfunction "C_C") (pintype "passive"))
    )
    (net (code "44") (name "Net-(D24-PadC)") (class "Default")
      (node (ref "D24") (pin "C") (pinfunction "C_C") (pintype "passive"))
      (node (ref "D25") (pin "C") (pinfunction "C_C") (pintype "passive"))
      (node (ref "D29") (pin "C") (pinfunction "C_C") (pintype "passive"))
      (node (ref "R15") (pin "2") (pinfunction "2_2") (pintype "passive"))
    )
    (net (code "45") (name "Net-(D25-PadA)") (class "Default")
      (node (ref "D25") (pin "A") (pinfunction "A_A") (pintype "passive"))
      (node (ref "D26") (pin "C") (pinfunction "C_C") (pintype "passive"))
    )
    (net (code "46") (name "Net-(D27-PadC)") (class "Default")
      (node (ref "D27") (pin "C") (pinfunction "C_C") (pintype "passive"))
      (node (ref "D30") (pin "C") (pinfunction "C_C") (pintype "passive"))
      (node (ref "R17") (pin "2") (pinfunction "2_2") (pintype "passive"))
    )
    (net (code "47") (name "Net-(D30-PadA)") (class "Default")
      (node (ref "D30") (pin "A") (pinfunction "A_A") (pintype "passive"))
      (node (ref "D31") (pin "C") (pinfunction "C_C") (pintype "passive"))
    )
    (net (code "48") (name "Net-(D34-PadC)") (class "Default")
      (node (ref "D34") (pin "C") (pinfunction "C_C") (pintype "passive"))
      (node (ref "D38") (pin "C") (pinfunction "C_C") (pintype "passive"))
      (node (ref "R23") (pin "2") (pinfunction "2_2") (pintype "passive"))
    )
    (net (code "49") (name "Net-(D35-PadA)") (class "Default")
      (node (ref "D35") (pin "A") (pinfunction "A_A") (pintype "passive"))
      (node (ref "D36") (pin "C") (pinfunction "C_C") (pintype "passive"))
    )
    (net (code "50") (name "Net-(D38-PadA)") (class "Default")
      (node (ref "D38") (pin "A") (pinfunction "A_A") (pintype "passive"))
      (node (ref "D39") (pin "C") (pinfunction "C_C") (pintype "passive"))
    )
    (net (code "51") (name "Net-(D40-PadC)") (class "Default")
      (node (ref "D40") (pin "C") (pinfunction "C_C") (pintype "passive"))
      (node (ref "D41") (pin "C") (pinfunction "C_C") (pintype "passive"))
      (node (ref "R25") (pin "2") (pinfunction "2_2") (pintype "passive"))
    )
    (net (code "52") (name "Net-(D41-PadA)") (class "Default")
      (node (ref "D41") (pin "A") (pinfunction "A_A") (pintype "passive"))
      (node (ref "D42") (pin "C") (pinfunction "C_C") (pintype "passive"))
    )
    (net (code "53") (name "Net-(D43-PadC)") (class "Default")
      (node (ref "D43") (pin "C") (pinfunction "C_C") (pintype "passive"))
      (node (ref "D45") (pin "C") (pinfunction "C_C") (pintype "passive"))
      (node (ref "R28") (pin "2") (pinfunction "2_2") (pintype "passive"))
    )
    (net (code "54") (name "Net-(D45-PadA)") (class "Default")
      (node (ref "D45") (pin "A") (pinfunction "A_A") (pintype "passive"))
      (node (ref "D46") (pin "C") (pinfunction "C_C") (pintype "passive"))
    )
    (net (code "55") (name "Net-(D50-PadC)") (class "Default")
      (node (ref "D50") (pin "C") (pinfunction "C_C") (pintype "passive"))
      (node (ref "D52") (pin "C") (pinfunction "C_C") (pintype "passive"))
      (node (ref "D56") (pin "C") (pinfunction "C_C") (pintype "passive"))
      (node (ref "R32") (pin "2") (pinfunction "2_2") (pintype "passive"))
    )
    (net (code "56") (name "Net-(D52-PadA)") (class "Default")
      (node (ref "D52") (pin "A") (pinfunction "A_A") (pintype "passive"))
      (node (ref "D53") (pin "C") (pinfunction "C_C") (pintype "passive"))
    )
    (net (code "57") (name "Net-(D54-PadC)") (class "Default")
      (node (ref "D54") (pin "C") (pinfunction "C_C") (pintype "passive"))
      (node (ref "D57") (pin "C") (pinfunction "C_C") (pintype "passive"))
      (node (ref "R35") (pin "2") (pinfunction "2_2") (pintype "passive"))
    )
    (net (code "58") (name "Net-(D57-PadA)") (class "Default")
      (node (ref "D57") (pin "A") (pinfunction "A_A") (pintype "passive"))
      (node (ref "D60") (pin "C") (pinfunction "C_C") (pintype "passive"))
    )
    (net (code "59") (name "Net-(D58-PadA)") (class "Default")
      (node (ref "D58") (pin "A") (pinfunction "A_A") (pintype "passive"))
      (node (ref "D59") (pin "C") (pinfunction "C_C") (pintype "passive"))
    )
    (net (code "60") (name "Net-(D58-PadC)") (class "Default")
      (node (ref "D58") (pin "C") (pinfunction "C_C") (pintype "passive"))
      (node (ref "D62") (pin "C") (pinfunction "C_C") (pintype "passive"))
      (node (ref "R36") (pin "2") (pinfunction "2_2") (pintype "passive"))
    )
    (net (code "61") (name "Net-(D64-PadC)") (class "Default")
      (node (ref "D64") (pin "C") (pinfunction "C_C") (pintype "passive"))
      (node (ref "D67") (pin "C") (pinfunction "C_C") (pintype "passive"))
      (node (ref "R44") (pin "2") (pinfunction "2_2") (pintype "passive"))
    )
    (net (code "62") (name "Net-(D65-PadA)") (class "Default")
      (node (ref "D65") (pin "A") (pinfunction "A_A") (pintype "passive"))
      (node (ref "D66") (pin "C") (pinfunction "C_C") (pintype "passive"))
    )
    (net (code "63") (name "Net-(D65-PadC)") (class "Default")
      (node (ref "D65") (pin "C") (pinfunction "C_C") (pintype "passive"))
      (node (ref "D69") (pin "C") (pinfunction "C_C") (pintype "passive"))
      (node (ref "D70") (pin "C") (pinfunction "C_C") (pintype "passive"))
      (node (ref "R42") (pin "2") (pinfunction "2_2") (pintype "passive"))
    )
    (net (code "64") (name "Net-(D67-PadA)") (class "Default")
      (node (ref "D67") (pin "A") (pinfunction "A_A") (pintype "passive"))
      (node (ref "D68") (pin "C") (pinfunction "C_C") (pintype "passive"))
    )
    (net (code "65") (name "Net-(D73-PadC)") (class "Default")
      (node (ref "D73") (pin "C") (pinfunction "C_C") (pintype "passive"))
      (node (ref "D74") (pin "C") (pinfunction "C_C") (pintype "passive"))
      (node (ref "D75") (pin "C") (pinfunction "C_C") (pintype "passive"))
      (node (ref "D76") (pin "C") (pinfunction "C_C") (pintype "passive"))
      (node (ref "D82") (pin "C") (pinfunction "C_C") (pintype "passive"))
      (node (ref "R47") (pin "2") (pinfunction "2_2") (pintype "passive"))
    )
    (net (code "66") (name "Net-(D76-PadA)") (class "Default")
      (node (ref "D76") (pin "A") (pinfunction "A_A") (pintype "passive"))
      (node (ref "D77") (pin "C") (pinfunction "C_C") (pintype "passive"))
    )
    (net (code "67") (name "Net-(D78-PadC)") (class "Default")
      (node (ref "D78") (pin "C") (pinfunction "C_C") (pintype "passive"))
      (node (ref "D79") (pin "C") (pinfunction "C_C") (pintype "passive"))
      (node (ref "R49") (pin "2") (pinfunction "2_2") (pintype "passive"))
    )
    (net (code "68") (name "Net-(D79-PadA)") (class "Default")
      (node (ref "D79") (pin "A") (pinfunction "A_A") (pintype "passive"))
      (node (ref "D80") (pin "C") (pinfunction "C_C") (pintype "passive"))
    )
    (net (code "69") (name "Net-(D86-PadC)") (class "Default")
      (node (ref "D86") (pin "C") (pinfunction "C_C") (pintype "passive"))
      (node (ref "D90") (pin "C") (pinfunction "C_C") (pintype "passive"))
      (node (ref "R56") (pin "2") (pinfunction "2_2") (pintype "passive"))
    )
    (net (code "70") (name "Net-(D87-PadC)") (class "Default")
      (node (ref "D87") (pin "C") (pinfunction "C_C") (pintype "passive"))
      (node (ref "D88") (pin "C") (pinfunction "C_C") (pintype "passive"))
      (node (ref "R54") (pin "2") (pinfunction "2_2") (pintype "passive"))
    )
    (net (code "71") (name "Net-(D88-PadA)") (class "Default")
      (node (ref "D88") (pin "A") (pinfunction "A_A") (pintype "passive"))
      (node (ref "D89") (pin "C") (pinfunction "C_C") (pintype "passive"))
    )
    (net (code "72") (name "Net-(D90-PadA)") (class "Default")
      (node (ref "D90") (pin "A") (pinfunction "A_A") (pintype "passive"))
      (node (ref "D91") (pin "C") (pinfunction "C_C") (pintype "passive"))
    )
    (net (code "73") (name "Net-(D93-PadC)") (class "Default")
      (node (ref "D93") (pin "C") (pinfunction "C_C") (pintype "passive"))
      (node (ref "D94") (pin "C") (pinfunction "C_C") (pintype "passive"))
      (node (ref "R58") (pin "2") (pinfunction "2_2") (pintype "passive"))
    )
    (net (code "74") (name "Net-(D94-PadA)") (class "Default")
      (node (ref "D94") (pin "A") (pinfunction "A_A") (pintype "passive"))
      (node (ref "D95") (pin "C") (pinfunction "C_C") (pintype "passive"))
    )
    (net (code "75") (name "Net-(D101-PadC)") (class "Default")
      (node (ref "D101") (pin "C") (pinfunction "C_C") (pintype "passive"))
      (node (ref "D102") (pin "C") (pinfunction "C_C") (pintype "passive"))
      (node (ref "R63") (pin "2") (pinfunction "2_2") (pintype "passive"))
    )
    (net (code "76") (name "Net-(D102-PadA)") (class "Default")
      (node (ref "D102") (pin "A") (pinfunction "A_A") (pintype "passive"))
      (node (ref "D103") (pin "C") (pinfunction "C_C") (pintype "passive"))
    )
    (net (code "77") (name "Net-(D104-PadA)") (class "Default")
      (node (ref "D104") (pin "A") (pinfunction "A_A") (pintype "passive"))
      (node (ref "D105") (pin "C") (pinfunction "C_C") (pintype "passive"))
    )
    (net (code "78") (name "Net-(D105-PadA)") (class "Default")
      (node (ref "D105") (pin "A") (pinfunction "A_A") (pintype "passive"))
      (node (ref "D106") (pin "C") (pinfunction "C_C") (pintype "passive"))
    )
    (net (code "79") (name "Net-(Q1-B)") (class "Default")
      (node (ref "C1") (pin "1") (pinfunction "1_1") (pintype "passive"))
      (node (ref "D3") (pin "A") (pinfunction "A_A") (pintype "passive"))
      (node (ref "Q1") (pin "2") (pinfunction "B_2") (pintype "passive"))
      (node (ref "R2") (pin "1") (pinfunction "1_1") (pintype "passive"))
    )
    (net (code "80") (name "Net-(Q2-B)") (class "Default")
      (node (ref "D7") (pin "A") (pinfunction "A_A") (pintype "passive"))
      (node (ref "D8") (pin "C") (pinfunction "C_C") (pintype "passive"))
      (node (ref "Q2") (pin "2") (pinfunction "B_2") (pintype "passive"))
      (node (ref "R5") (pin "1") (pinfunction "1_1") (pintype "passive"))
    )
    (net (code "81") (name "Net-(Q2-C)") (class "Default")
      (node (ref "C1") (pin "2") (pinfunction "2_2") (pintype "passive"))
      (node (ref "D5") (pin "C") (pinfunction "C_C") (pintype "passive"))
      (node (ref "Q2") (pin "3") (pinfunction "C_3") (pintype "passive"))
      (node (ref "R3") (pin "2") (pinfunction "2_2") (pintype "passive"))
    )
    (net (code "82") (name "Net-(Q3-B)") (class "Default")
      (node (ref "D12") (pin "A") (pinfunction "A_A") (pintype "passive"))
      (node (ref "Q3") (pin "2") (pinfunction "B_2") (pintype "passive"))
      (node (ref "R9") (pin "1") (pinfunction "1_1") (pintype "passive"))
    )
    (net (code "83") (name "Net-(Q3-C)") (class "Default")
      (node (ref "D14") (pin "A") (pinfunction "A_A") (pintype "passive"))
      (node (ref "D15") (pin "C") (pinfunction "C_C") (pintype "passive"))
      (node (ref "Q3") (pin "3") (pinfunction "C_3") (pintype "passive"))
      (node (ref "R10") (pin "2") (pinfunction "2_2") (pintype "passive"))
    )
    (net (code "84") (name "Net-(Q4-B)") (class "Default")
      (node (ref "D19") (pin "A") (pinfunction "A_A") (pintype "passive"))
      (node (ref "Q4") (pin "2") (pinfunction "B_2") (pintype "passive"))
      (node (ref "R13") (pin "1") (pinfunction "1_1") (pintype "passive"))
    )
    (net (code "85") (name "Net-(Q5-B)") (class "Default")
      (node (ref "D23") (pin "C") (pinfunction "C_C") (pintype "passive"))
      (node (ref "D26") (pin "A") (pinfunction "A_A") (pintype "passive"))
      (node (ref "Q5") (pin "2") (pinfunction "B_2") (pintype "passive"))
      (node (ref "R16") (pin "1") (pinfunction "1_1") (pintype "passive"))
    )
    (net (code "86") (name "Net-(Q6-B)") (class "Default")
      (node (ref "D36") (pin "A") (pinfunction "A_A") (pintype "passive"))
      (node (ref "Q6") (pin "2") (pinfunction "B_2") (pintype "passive"))
      (node (ref "R22") (pin "1") (pinfunction "1_1") (pintype "passive"))
    )
    (net (code "87") (name "Net-(Q7-B)") (class "Default")
      (node (ref "D31") (pin "A") (pinfunction "A_A") (pintype "passive"))
      (node (ref "Q7") (pin "2") (pinfunction "B_2") (pintype "passive"))
      (node (ref "R19") (pin "1") (pinfunction "1_1") (pintype "passive"))
    )
    (net (code "88") (name "Net-(Q8-B)") (class "Default")
      (node (ref "D39") (pin "A") (pinfunction "A_A") (pintype "passive"))
      (node (ref "Q8") (pin "2") (pinfunction "B_2") (pintype "passive"))
      (node (ref "R24") (pin "1") (pinfunction "1_1") (pintype "passive"))
    )
    (net (code "89") (name "Net-(Q9-B)") (class "Default")
      (node (ref "D42") (pin "A") (pinfunction "A_A") (pintype "passive"))
      (node (ref "Q9") (pin "2") (pinfunction "B_2") (pintype "passive"))
      (node (ref "R27") (pin "1") (pinfunction "1_1") (pintype "passive"))
    )
    (net (code "90") (name "Net-(Q10-B)") (class "Default")
      (node (ref "D46") (pin "A") (pinfunction "A_A") (pintype "passive"))
      (node (ref "Q10") (pin "2") (pinfunction "B_2") (pintype "passive"))
      (node (ref "R29") (pin "1") (pinfunction "1_1") (pintype "passive"))
    )
    (net (code "91") (name "Net-(Q10-C)") (class "Default")
      (node (ref "D24") (pin "A") (pinfunction "A_A") (pintype "passive"))
      (node (ref "D49") (pin "C") (pinfunction "C_C") (pintype "passive"))
      (node (ref "D50") (pin "A") (pinfunction "A_A") (pintype "passive"))
      (node (ref "D74") (pin "A") (pinfunction "A_A") (pintype "passive"))
      (node (ref "Q10") (pin "3") (pinfunction "C_3") (pintype "passive"))
      (node (ref "R31") (pin "2") (pinfunction "2_2") (pintype "passive"))
    )
    (net (code "92") (name "Net-(Q11-B)") (class "Default")
      (node (ref "D59") (pin "A") (pinfunction "A_A") (pintype "passive"))
      (node (ref "Q11") (pin "2") (pinfunction "B_2") (pintype "passive"))
      (node (ref "R37") (pin "1") (pinfunction "1_1") (pintype "passive"))
    )
    (net (code "93") (name "Net-(Q12-B)") (class "Default")
      (node (ref "D48") (pin "C") (pinfunction "C_C") (pintype "passive"))
      (node (ref "D53") (pin "A") (pinfunction "A_A") (pintype "passive"))
      (node (ref "Q12") (pin "2") (pinfunction "B_2") (pintype "passive"))
      (node (ref "R33") (pin "1") (pinfunction "1_1") (pintype "passive"))
    )
    (net (code "94") (name "Net-(Q13-B)") (class "Default")
      (node (ref "D66") (pin "A") (pinfunction "A_A") (pintype "passive"))
      (node (ref "Q13") (pin "2") (pinfunction "B_2") (pintype "passive"))
      (node (ref "R43") (pin "1") (pinfunction "1_1") (pintype "passive"))
    )
    (net (code "95") (name "Net-(Q13-C)") (class "Default")
      (node (ref "D61") (pin "C") (pinfunction "C_C") (pintype "passive"))
      (node (ref "D62") (pin "A") (pinfunction "A_A") (pintype "passive"))
      (node (ref "Q13") (pin "3") (pinfunction "C_3") (pintype "passive"))
      (node (ref "R40") (pin "2") (pinfunction "2_2") (pintype "passive"))
    )
    (net (code "96") (name "Net-(Q14-B)") (class "Default")
      (node (ref "D68") (pin "A") (pinfunction "A_A") (pintype "passive"))
      (node (ref "D71") (pin "C") (pinfunction "C_C") (pintype "passive"))
      (node (ref "Q14") (pin "2") (pinfunction "B_2") (pintype "passive"))
      (node (ref "R45") (pin "1") (pinfunction "1_1") (pintype "passive"))
    )
    (net (code "97") (name "Net-(Q15-B)") (class "Default")
      (node (ref "D60") (pin "A") (pinfunction "A_A") (pintype "passive"))
      (node (ref "Q15") (pin "2") (pinfunction "B_2") (pintype "passive"))
      (node (ref "R39") (pin "1") (pinfunction "1_1") (pintype "passive"))
    )
    (net (code "98") (name "Net-(Q16-B)") (class "Default")
      (node (ref "D77") (pin "A") (pinfunction "A_A") (pintype "passive"))
      (node (ref "Q16") (pin "2") (pinfunction "B_2") (pintype "passive"))
      (node (ref "R48") (pin "1") (pinfunction "1_1") (pintype "passive"))
    )
    (net (code "99") (name "Net-(Q17-B)") (class "Default")
      (node (ref "D80") (pin "A") (pinfunction "A_A") (pintype "passive"))
      (node (ref "Q17") (pin "2") (pinfunction "B_2") (pintype "passive"))
      (node (ref "R51") (pin "1") (pinfunction "1_1") (pintype "passive"))
    )
    (net (code "100") (name "Net-(Q18-B)") (class "Default")
      (node (ref "D91") (pin "A") (pinfunction "A_A") (pintype "passive"))
      (node (ref "D92") (pin "C") (pinfunction "C_C") (pintype "passive"))
      (node (ref "Q18") (pin "2") (pinfunction "B_2") (pintype "passive"))
      (node (ref "R57") (pin "1") (pinfunction "1_1") (pintype "passive"))
    )
    (net (code "101") (name "Net-(Q19-B)") (class "Default")
      (node (ref "D89") (pin "A") (pinfunction "A_A") (pintype "passive"))
      (node (ref "Q19") (pin "2") (pinfunction "B_2") (pintype "passive"))
      (node (ref "R55") (pin "1") (pinfunction "1_1") (pintype "passive"))
    )
    (net (code "102") (name "Net-(Q20-B)") (class "Default")
      (node (ref "D103") (pin "A") (pinfunction "A_A") (pintype "passive"))
      (node (ref "Q20") (pin "2") (pinfunction "B_2") (pintype "passive"))
      (node (ref "R64") (pin "1") (pinfunction "1_1") (pintype "passive"))
    )
    (net (code "103") (name "Net-(Q20-C)") (class "Default")
      (node (ref "D100") (pin "C") (pinfunction "C_C") (pintype "passive"))
      (node (ref "D21") (pin "A") (pinfunction "A_A") (pintype "passive"))
      (node (ref "D44") (pin "A") (pinfunction "A_A") (pintype "passive"))
      (node (ref "D84") (pin "A") (pinfunction "A_A") (pintype "passive"))
      (node (ref "D98") (pin "A") (pinfunction "A_A") (pintype "passive"))
      (node (ref "Q20") (pin "3") (pinfunction "C_3") (pintype "passive"))
      (node (ref "R62") (pin "2") (pinfunction "2_2") (pintype "passive"))
    )
    (net (code "104") (name "Net-(Q21-B)") (class "Default")
      (node (ref "D95") (pin "A") (pinfunction "A_A") (pintype "passive"))
      (node (ref "Q21") (pin "2") (pinfunction "B_2") (pintype "passive"))
      (node (ref "R60") (pin "1") (pinfunction "1_1") (pintype "passive"))
    )
    (net (code "105") (name "VCC") (class "Default")
      (node (ref "A") (pin "A2") (pinfunction "P_A2") (pintype "passive"))
      (node (ref "R13") (pin "2") (pinfunction "2_2") (pintype "passive"))
      (node (ref "R16") (pin "2") (pinfunction "2_2") (pintype "passive"))
      (node (ref "R19") (pin "2") (pinfunction "2_2") (pintype "passive"))
      (node (ref "R2") (pin "2") (pinfunction "2_2") (pintype "passive"))
      (node (ref "R22") (pin "2") (pinfunction "2_2") (pintype "passive"))
      (node (ref "R24") (pin "2") (pinfunction "2_2") (pintype "passive"))
      (node (ref "R27") (pin "2") (pinfunction "2_2") (pintype "passive"))
      (node (ref "R29") (pin "2") (pinfunction "2_2") (pintype "passive"))
      (node (ref "R33") (pin "2") (pinfunction "2_2") (pintype "passive"))
      (node (ref "R37") (pin "2") (pinfunction "2_2") (pintype "passive"))
      (node (ref "R39") (pin "2") (pinfunction "2_2") (pintype "passive"))
      (node (ref "R43") (pin "2") (pinfunction "2_2") (pintype "passive"))
      (node (ref "R45") (pin "2") (pinfunction "2_2") (pintype "passive"))
      (node (ref "R48") (pin "2") (pinfunction "2_2") (pintype "passive"))
      (node (ref "R5") (pin "2") (pinfunction "2_2") (pintype "passive"))
      (node (ref "R51") (pin "2") (pinfunction "2_2") (pintype "passive"))
      (node (ref "R55") (pin "2") (pinfunction "2_2") (pintype "passive"))
      (node (ref "R57") (pin "2") (pinfunction "2_2") (pintype "passive"))
      (node (ref "R60") (pin "2") (pinfunction "2_2") (pintype "passive"))
      (node (ref "R64") (pin "2") (pinfunction "2_2") (pintype "passive"))
      (node (ref "R9") (pin "2") (pinfunction "2_2") (pintype "passive"))
    )
  )
)
